# powerB.net
KiCad netlist of a schematic drawn in Altium Designer
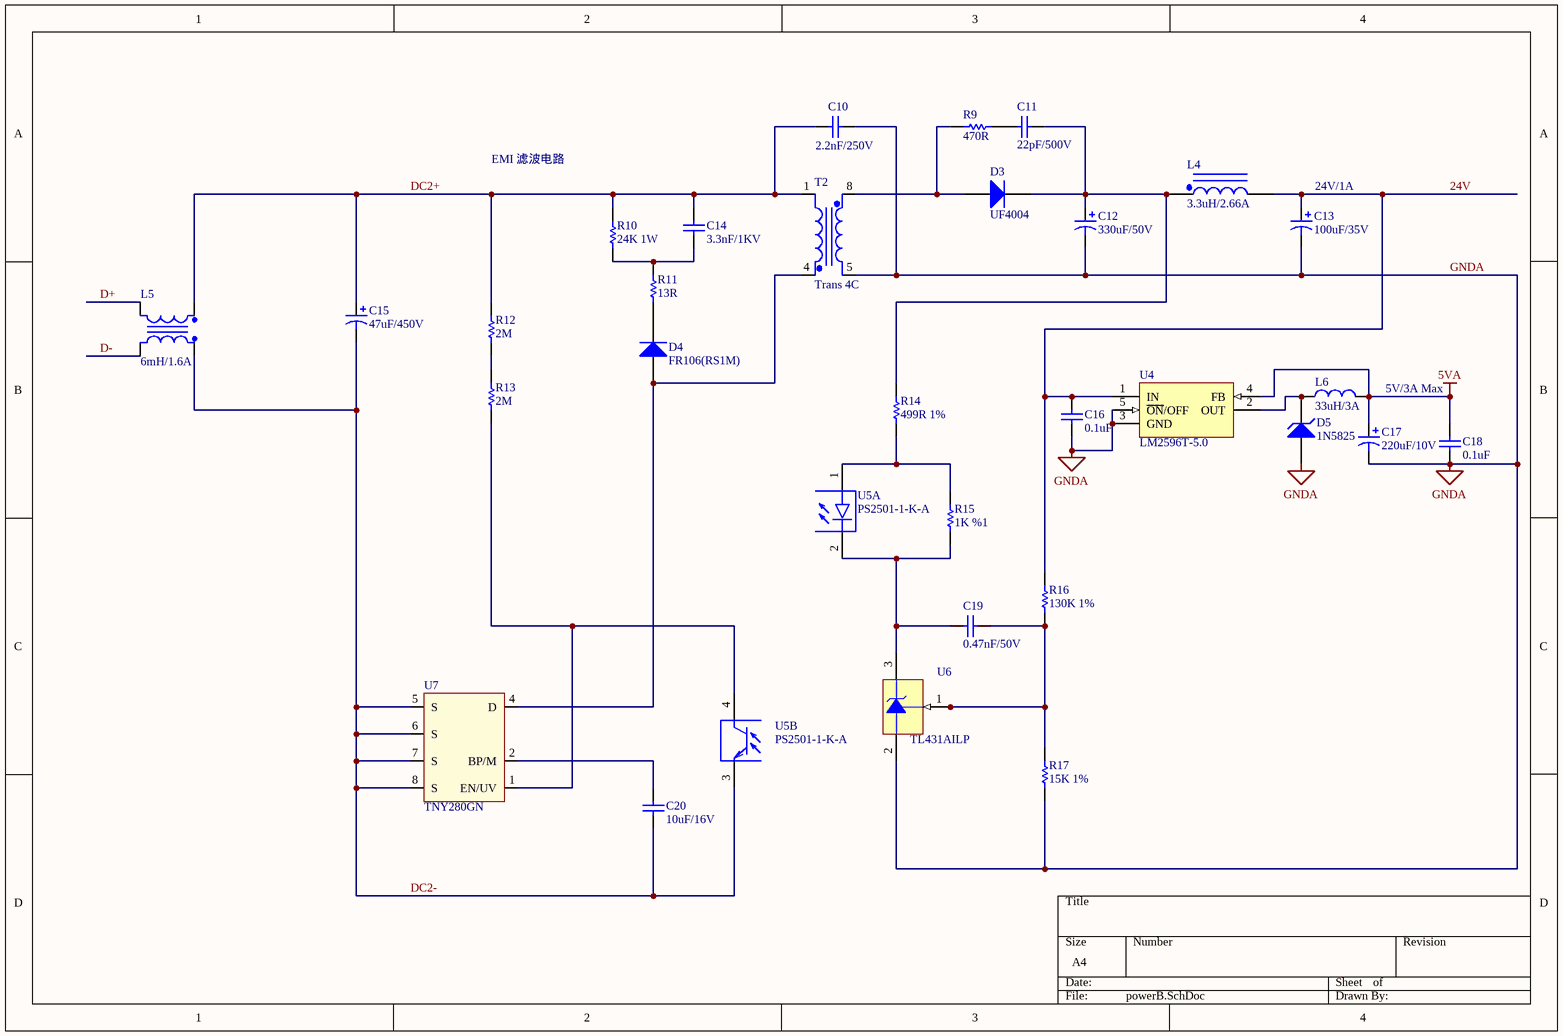
[diagram p0: powerB.SchDoc]

(export (version "E")
  (design (tool "Eeschema 10.0.6"))
  (components
    (comp (ref "C10")
      (value "2.2nF/250V")
      (footprint "CAPRD5-9x3B")
      (description "Capacitor")
      (fields (field (name "PUBLISHER") "Altium Limited"))
      (libsource (lib "Miscellaneous Devices") (part "Cap"))
    )
    (comp (ref "C11")
      (value "22pF/500V")
      (footprint "CAPC3216M")
      (description "Capacitor")
      (fields (field (name "PUBLISHER") "Altium Limited"))
      (libsource (lib "Miscellaneous Devices") (part "Cap"))
    )
    (comp (ref "C12")
      (value "330uF/50V")
      (footprint "CAPPR5-10x16")
      (description "Polarized Capacitor (Radial)")
      (fields (field (name "PUBLISHER") "Altium Limited"))
      (libsource (lib "Miscellaneous Devices") (part "Cap Pol1"))
    )
    (comp (ref "C13")
      (value "100uF/35V")
      (footprint "CAPPR2.5-6.3x11.5")
      (description "Polarized Capacitor (Radial)")
      (fields (field (name "PUBLISHER") "Altium Limited"))
      (libsource (lib "Miscellaneous Devices") (part "Cap Pol1"))
    )
    (comp (ref "C14")
      (value "3.3nF/1KV")
      (footprint "CAPRD5-4.5x3A")
      (description "Capacitor")
      (fields (field (name "PUBLISHER") "Altium Limited"))
      (libsource (lib "Miscellaneous Devices") (part "Cap"))
    )
    (comp (ref "C15")
      (value "47uF/450V")
      (footprint "CAPPR7.5-18x25A")
      (description "Polarized Capacitor (Radial)")
      (fields (field (name "PUBLISHER") "Altium Limited"))
      (libsource (lib "Miscellaneous Devices") (part "Cap Pol1"))
    )
    (comp (ref "C16")
      (value "0.1uF")
      (footprint "CAPC3216M")
      (description "Capacitor")
      (fields (field (name "PUBLISHER") "Altium Limited"))
      (libsource (lib "Miscellaneous Devices") (part "Cap"))
    )
    (comp (ref "C17")
      (value "220uF/10V")
      (footprint "CAPPR2.5-6.3x11.5")
      (description "Polarized Capacitor (Radial)")
      (fields (field (name "PUBLISHER") "Altium Limited"))
      (libsource (lib "Miscellaneous Devices") (part "Cap Pol1"))
    )
    (comp (ref "C18")
      (value "0.1uF")
      (footprint "CAPC3216M")
      (description "Capacitor")
      (fields (field (name "PUBLISHER") "Altium Limited"))
      (libsource (lib "Miscellaneous Devices") (part "Cap"))
    )
    (comp (ref "C19")
      (value "0.47nF/50V")
      (footprint "CAPC3216M")
      (description "Capacitor")
      (fields (field (name "PUBLISHER") "Altium Limited"))
      (libsource (lib "Miscellaneous Devices") (part "Cap"))
    )
    (comp (ref "C20")
      (value "10uF/16V")
      (footprint "CAPC3216M")
      (description "Capacitor")
      (fields (field (name "PUBLISHER") "Altium Limited"))
      (libsource (lib "Miscellaneous Devices") (part "Cap"))
    )
    (comp (ref "D3")
      (value "UF4004")
      (footprint "SMA")
      (description "High Conductance Fast Diode")
      (fields (field (name "PUBLISHER") "Altium Limited"))
      (libsource (lib "Miscellaneous Devices") (part "Diode 1N4148"))
    )
    (comp (ref "D4")
      (value "FR106(RS1M)")
      (footprint "SMA")
      (description "High Conductance Fast Diode")
      (fields (field (name "PUBLISHER") "Altium Limited"))
      (libsource (lib "Miscellaneous Devices") (part "Diode 1N4148"))
    )
    (comp (ref "D5")
      (value "1N5825")
      (footprint "SMB")
      (description "Zener Diode")
      (fields (field (name "PUBLISHER") "Altium Limited"))
      (libsource (lib "Miscellaneous Devices") (part "D Zener"))
    )
    (comp (ref "L4")
      (value "3.3uH/2.66A")
      (footprint "L0810")
      (description "Magnetic-Core Inductor with Winding Polarity Marking")
      (fields (field (name "PUBLISHER") "Altium Limited"))
      (libsource (lib "Miscellaneous Devices") (part "Inductor Iron Dot"))
    )
    (comp (ref "L5")
      (value "6mH/1.6A")
      (footprint "TRF_4A")
      (description "Conjugate stream coil,pitch 7.62mmx8mm(LxW)")
      (fields (field (name "PUBLISHER") "Altium Limited"))
      (libsource (lib "UserLib") (part "Inductor Iron Dot Inphase"))
    )
    (comp (ref "L6")
      (value "33uH/3A")
      (footprint "L0810")
      (description "Inductor with Winding No Polarity Marking")
      (fields (field (name "PUBLISHER") "Altium Limited"))
      (libsource (lib "UserLib") (part "Inductor"))
    )
    (comp (ref "R9")
      (value "470R")
      (footprint "RESC3216M")
      (description "Metal film Resistor")
      (fields (field (name "PUBLISHER") "Altium Limited"))
      (libsource (lib "Miscellaneous Devices") (part "Res Semi"))
    )
    (comp (ref "R10")
      (value "24K 1W")
      (footprint "RES13.55-11.5X4.2")
      (description "Metal film Resistor")
      (fields (field (name "PUBLISHER") "Altium Limited"))
      (libsource (lib "Miscellaneous Devices") (part "Res Semi"))
    )
    (comp (ref "R11")
      (value "13R")
      (footprint "RESC3216M")
      (description "Metal film Resistor")
      (fields (field (name "PUBLISHER") "Altium Limited"))
      (libsource (lib "Miscellaneous Devices") (part "Res Semi"))
    )
    (comp (ref "R12")
      (value "2M")
      (footprint "RESC3216M")
      (description "Metal film Resistor")
      (fields (field (name "PUBLISHER") "Altium Limited"))
      (libsource (lib "Miscellaneous Devices") (part "Res Semi"))
    )
    (comp (ref "R13")
      (value "2M")
      (footprint "RESC3216M")
      (description "Metal film Resistor")
      (fields (field (name "PUBLISHER") "Altium Limited"))
      (libsource (lib "Miscellaneous Devices") (part "Res Semi"))
    )
    (comp (ref "R14")
      (value "499R 1%")
      (footprint "RESC3216M")
      (description "Metal film Resistor")
      (fields (field (name "PUBLISHER") "Altium Limited"))
      (libsource (lib "Miscellaneous Devices") (part "Res Semi"))
    )
    (comp (ref "R15")
      (value "1K %1")
      (footprint "RESC3216M")
      (description "Metal film Resistor")
      (fields (field (name "PUBLISHER") "Altium Limited"))
      (libsource (lib "Miscellaneous Devices") (part "Res Semi"))
    )
    (comp (ref "R16")
      (value "130K 1%")
      (footprint "RESC3216M")
      (description "Metal film Resistor")
      (fields (field (name "PUBLISHER") "Altium Limited"))
      (libsource (lib "Miscellaneous Devices") (part "Res Semi"))
    )
    (comp (ref "R17")
      (value "15K 1%")
      (footprint "RESC3216M")
      (description "Metal film Resistor")
      (fields (field (name "PUBLISHER") "Altium Limited"))
      (libsource (lib "Miscellaneous Devices") (part "Res Semi"))
    )
    (comp (ref "T2")
      (value "Trans 4C")
      (footprint "EE22W(2+2)")
      (description "Transformer")
      (fields (field (name "PUBLISHER") "Altium Limited"))
      (libsource (lib "UserSchDev") (part "Trans 4C"))
    )
    (comp (ref "U4")
      (value "LM2596T-5.0")
      (footprint "TO-220-5")
      (description "5V稳压芯片")
      (fields (field (name "PUBLISHER") "Altium Limited"))
      (libsource (lib "UserSchDev") (part "LM2596T-5.0"))
    )
    (comp (ref "U5")
      (value "PS2501-1-K-A")
      (footprint "SOP-4")
      (description "Single-Supply Dual Operational Amplifier,10MHz")
      (fields (field (name "PUBLISHER") "Altium Limited"))
      (libsource (lib "UserLib") (part "PC817D"))
    )
    (comp (ref "U6")
      (value "TL431AILP")
      (footprint "TO-92AA")
      (description "Programmable Precision Reference")
      (fields (field (name "PUBLISHER") "Altium Limited"))
      (libsource (lib "ON Semi Power Mgt Voltage Reference") (part "TL431CLP"))
    )
    (comp (ref "U7") (value "TNY280GN") (footprint "SMD-8C") (libsource (lib "UserLib") (part "TNY279PN")))
  )
  (nets
    (net (code "1") (name "/24V") (class "Default")
      (node (ref "C13") (pin "1") (pinfunction "1_1") (pintype "passive"))
      (node (ref "C16") (pin "1") (pinfunction "1_1") (pintype "passive"))
      (node (ref "L4") (pin "2") (pinfunction "2_2") (pintype "passive"))
      (node (ref "R16") (pin "2") (pinfunction "2_2") (pintype "passive"))
      (node (ref "U4") (pin "1") (pinfunction "IN_1") (pintype "power_in"))
    )
    (net (code "2") (name "/D+") (class "Default")
      (node (ref "L5") (pin "4") (pinfunction "Sec-_4") (pintype "passive"))
    )
    (net (code "3") (name "/D-") (class "Default")
      (node (ref "L5") (pin "3") (pinfunction "Pri-_3") (pintype "passive"))
    )
    (net (code "4") (name "/DC2+") (class "Default")
      (node (ref "C10") (pin "1") (pinfunction "1_1") (pintype "passive"))
      (node (ref "C14") (pin "1") (pinfunction "1_1") (pintype "passive"))
      (node (ref "C15") (pin "1") (pinfunction "1_1") (pintype "passive"))
      (node (ref "L5") (pin "2") (pinfunction "Sec+_2") (pintype "passive"))
      (node (ref "R10") (pin "1") (pinfunction "1_1") (pintype "passive"))
      (node (ref "R12") (pin "2") (pinfunction "2_2") (pintype "passive"))
      (node (ref "T2") (pin "1") (pinfunction "Pri+_1") (pintype "passive"))
    )
    (net (code "5") (name "/DC2-") (class "Default")
      (node (ref "C15") (pin "2") (pinfunction "2_2") (pintype "passive"))
      (node (ref "C20") (pin "2") (pinfunction "2_2") (pintype "passive"))
      (node (ref "L5") (pin "1") (pinfunction "Pri+_1") (pintype "passive"))
      (node (ref "U5") (pin "3") (pinfunction "E_3") (pintype "passive"))
      (node (ref "U7") (pin "5") (pinfunction "S_5") (pintype "passive"))
      (node (ref "U7") (pin "6") (pinfunction "S_6") (pintype "passive"))
      (node (ref "U7") (pin "7") (pinfunction "S_7") (pintype "passive"))
      (node (ref "U7") (pin "8") (pinfunction "S_8") (pintype "passive"))
    )
    (net (code "6") (name "5VA") (class "Default")
      (node (ref "C17") (pin "1") (pinfunction "1_1") (pintype "passive"))
      (node (ref "C18") (pin "2") (pinfunction "2_2") (pintype "passive"))
      (node (ref "L6") (pin "2") (pinfunction "2_2") (pintype "passive"))
      (node (ref "U4") (pin "4") (pinfunction "FB_4") (pintype "input"))
    )
    (net (code "7") (name "GNDA") (class "Default")
      (node (ref "C10") (pin "2") (pinfunction "2_2") (pintype "passive"))
      (node (ref "C12") (pin "2") (pinfunction "2_2") (pintype "passive"))
      (node (ref "C13") (pin "2") (pinfunction "2_2") (pintype "passive"))
      (node (ref "C16") (pin "2") (pinfunction "2_2") (pintype "passive"))
      (node (ref "C17") (pin "2") (pinfunction "2_2") (pintype "passive"))
      (node (ref "C18") (pin "1") (pinfunction "1_1") (pintype "passive"))
      (node (ref "D5") (pin "1") (pinfunction "A_1") (pintype "passive"))
      (node (ref "R17") (pin "1") (pinfunction "1_1") (pintype "passive"))
      (node (ref "T2") (pin "5") (pinfunction "Sec-_5") (pintype "passive"))
      (node (ref "U4") (pin "3") (pinfunction "GND_3") (pintype "power_in"))
      (node (ref "U4") (pin "5") (pinfunction "~{ON}/OFF_5") (pintype "input"))
      (node (ref "U6") (pin "2") (pinfunction "A_2") (pintype "passive"))
    )
    (net (code "8") (name "Net-(C11-Pad2)") (class "Default")
      (node (ref "C11") (pin "2") (pinfunction "2_2") (pintype "passive"))
      (node (ref "R9") (pin "1") (pinfunction "1_1") (pintype "passive"))
    )
    (net (code "9") (name "Net-(C14-Pad2)") (class "Default")
      (node (ref "C14") (pin "2") (pinfunction "2_2") (pintype "passive"))
      (node (ref "R10") (pin "2") (pinfunction "2_2") (pintype "passive"))
      (node (ref "R11") (pin "1") (pinfunction "1_1") (pintype "passive"))
    )
    (net (code "10") (name "Net-(D3-A)") (class "Default")
      (node (ref "D3") (pin "1") (pinfunction "A_1") (pintype "passive"))
      (node (ref "R9") (pin "2") (pinfunction "2_2") (pintype "passive"))
      (node (ref "T2") (pin "8") (pinfunction "Sec+_8") (pintype "passive"))
    )
    (net (code "11") (name "Net-(D3-K)") (class "Default")
      (node (ref "C11") (pin "1") (pinfunction "1_1") (pintype "passive"))
      (node (ref "C12") (pin "1") (pinfunction "1_1") (pintype "passive"))
      (node (ref "D3") (pin "2") (pinfunction "K_2") (pintype "passive"))
      (node (ref "L4") (pin "1") (pinfunction "1_1") (pintype "passive"))
      (node (ref "R14") (pin "2") (pinfunction "2_2") (pintype "passive"))
    )
    (net (code "12") (name "Net-(D4-A)") (class "Default")
      (node (ref "D4") (pin "1") (pinfunction "A_1") (pintype "passive"))
      (node (ref "T2") (pin "4") (pinfunction "Pri-_4") (pintype "passive"))
      (node (ref "U7") (pin "4") (pinfunction "D_4") (pintype "passive"))
    )
    (net (code "13") (name "Net-(D4-K)") (class "Default")
      (node (ref "D4") (pin "2") (pinfunction "K_2") (pintype "passive"))
      (node (ref "R11") (pin "2") (pinfunction "2_2") (pintype "passive"))
    )
    (net (code "14") (name "Net-(D5-K)") (class "Default")
      (node (ref "D5") (pin "2") (pinfunction "K_2") (pintype "passive"))
      (node (ref "L6") (pin "1") (pinfunction "1_1") (pintype "passive"))
      (node (ref "U4") (pin "2") (pinfunction "OUT_2") (pintype "power_in"))
    )
    (net (code "15") (name "Net-(R12-Pad1)") (class "Default")
      (node (ref "R12") (pin "1") (pinfunction "1_1") (pintype "passive"))
      (node (ref "R13") (pin "1") (pinfunction "1_1") (pintype "passive"))
    )
    (net (code "16") (name "Net-(U5A-+)") (class "Default")
      (node (ref "R14") (pin "1") (pinfunction "1_1") (pintype "passive"))
      (node (ref "R15") (pin "2") (pinfunction "2_2") (pintype "passive"))
      (node (ref "U5") (pin "1") (pinfunction "+_1") (pintype "passive"))
    )
    (net (code "17") (name "Net-(U5A--)") (class "Default")
      (node (ref "C19") (pin "2") (pinfunction "2_2") (pintype "passive"))
      (node (ref "R15") (pin "1") (pinfunction "1_1") (pintype "passive"))
      (node (ref "U5") (pin "2") (pinfunction "-_2") (pintype "passive"))
      (node (ref "U6") (pin "3") (pinfunction "K_3") (pintype "passive"))
    )
    (net (code "18") (name "Net-(U5B-C)") (class "Default")
      (node (ref "R13") (pin "2") (pinfunction "2_2") (pintype "passive"))
      (node (ref "U5") (pin "4") (pinfunction "C_4") (pintype "passive"))
      (node (ref "U7") (pin "1") (pinfunction "EN/UV_1") (pintype "passive"))
    )
    (net (code "19") (name "Net-(U6-REF)") (class "Default")
      (node (ref "C19") (pin "1") (pinfunction "1_1") (pintype "passive"))
      (node (ref "R16") (pin "1") (pinfunction "1_1") (pintype "passive"))
      (node (ref "R17") (pin "2") (pinfunction "2_2") (pintype "passive"))
      (node (ref "U6") (pin "1") (pinfunction "REF_1") (pintype "input"))
    )
    (net (code "20") (name "Net-(U7-BP{slash}M)") (class "Default")
      (node (ref "C20") (pin "1") (pinfunction "1_1") (pintype "passive"))
      (node (ref "U7") (pin "2") (pinfunction "BP/M_2") (pintype "passive"))
    )
  )
)
